# MAIN_SENSOR.net
KiCad netlist of a schematic drawn in Altium Designer
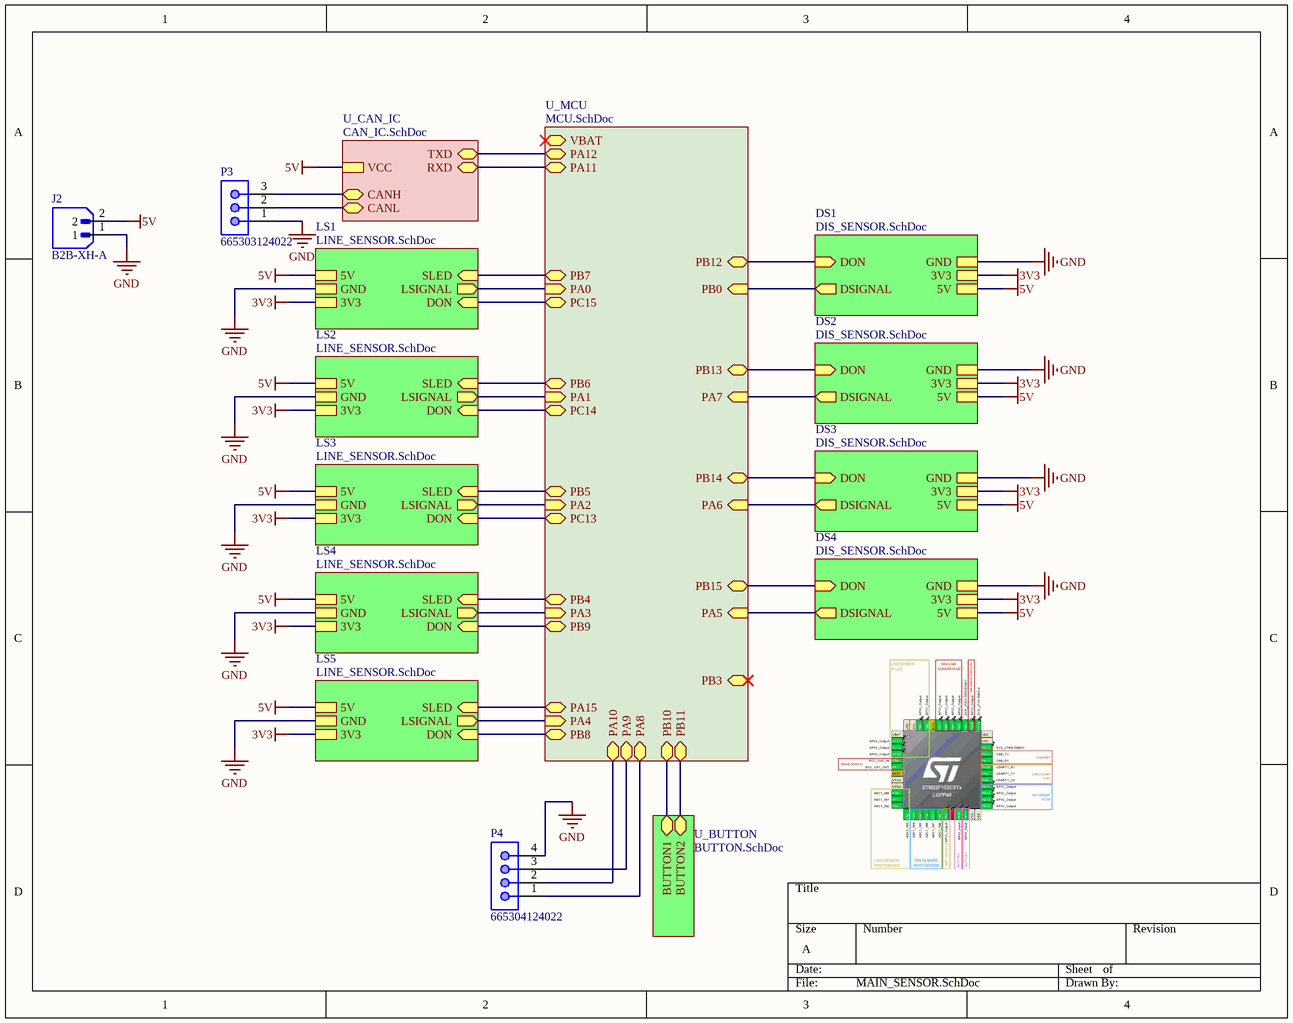
[diagram p0: MAIN_SENSOR.SchDoc]

(export (version "E")
  (design (tool "Eeschema 10.0.6"))
  (components
    (comp (ref "J2")
      (value "B2B-XH-A")
      (footprint "JST_B2B-XH-A")
      (fields (field (name "MF") "{'manufacturer': u'JST Sales America Inc.'}"))
      (libsource (lib "Header") (part "B2B-XH-A"))
    )
    (comp (ref "P3")
      (value "665303124022")
      (footprint "665303124022")
      (description "WR-WTB SMT Male Vertical Shrouded Header, pitch 1mm, 3p")
      (fields (field (name "PUBLISHER") "Wurth Elektronik"))
      (libsource (lib "Tin Tran") (part "665303124022"))
    )
    (comp (ref "P4")
      (value "665304124022")
      (footprint "665304124022")
      (description "WR-WTB SMT Male Vertical Shrouded Header, pitch 1mm, 4p")
      (fields (field (name "PUBLISHER") "Wurth Elektronik"))
      (libsource (lib "Tin Tran") (part "665304124022"))
    )
  )
  (nets
    (net (code "3") (name "/CANH") (class "Default")
      (node (ref "P3") (pin "3") (pinfunction "3_3") (pintype "passive"))
    )
    (net (code "4") (name "/CANL") (class "Default")
      (node (ref "P3") (pin "2") (pinfunction "2_2") (pintype "passive"))
    )
    (net (code "23") (name "/PA8") (class "Default")
      (node (ref "P4") (pin "1") (pinfunction "1_1") (pintype "passive"))
    )
    (net (code "24") (name "/PA9") (class "Default")
      (node (ref "P4") (pin "3") (pinfunction "3_3") (pintype "passive"))
    )
    (net (code "25") (name "/PA10") (class "Default")
      (node (ref "P4") (pin "2") (pinfunction "2_2") (pintype "passive"))
    )
    (net (code "36") (name "5V") (class "Default")
      (node (ref "J2") (pin "2") (pinfunction "2_2") (pintype "passive"))
    )
    (net (code "37") (name "GND") (class "Default")
      (node (ref "J2") (pin "1") (pinfunction "1_1") (pintype "passive"))
      (node (ref "P3") (pin "1") (pinfunction "1_1") (pintype "passive"))
      (node (ref "P4") (pin "4") (pinfunction "4_4") (pintype "passive"))
    )
  )
)
